# edition4-mainpart-4.net
KiCad netlist of a schematic drawn in EAGLE
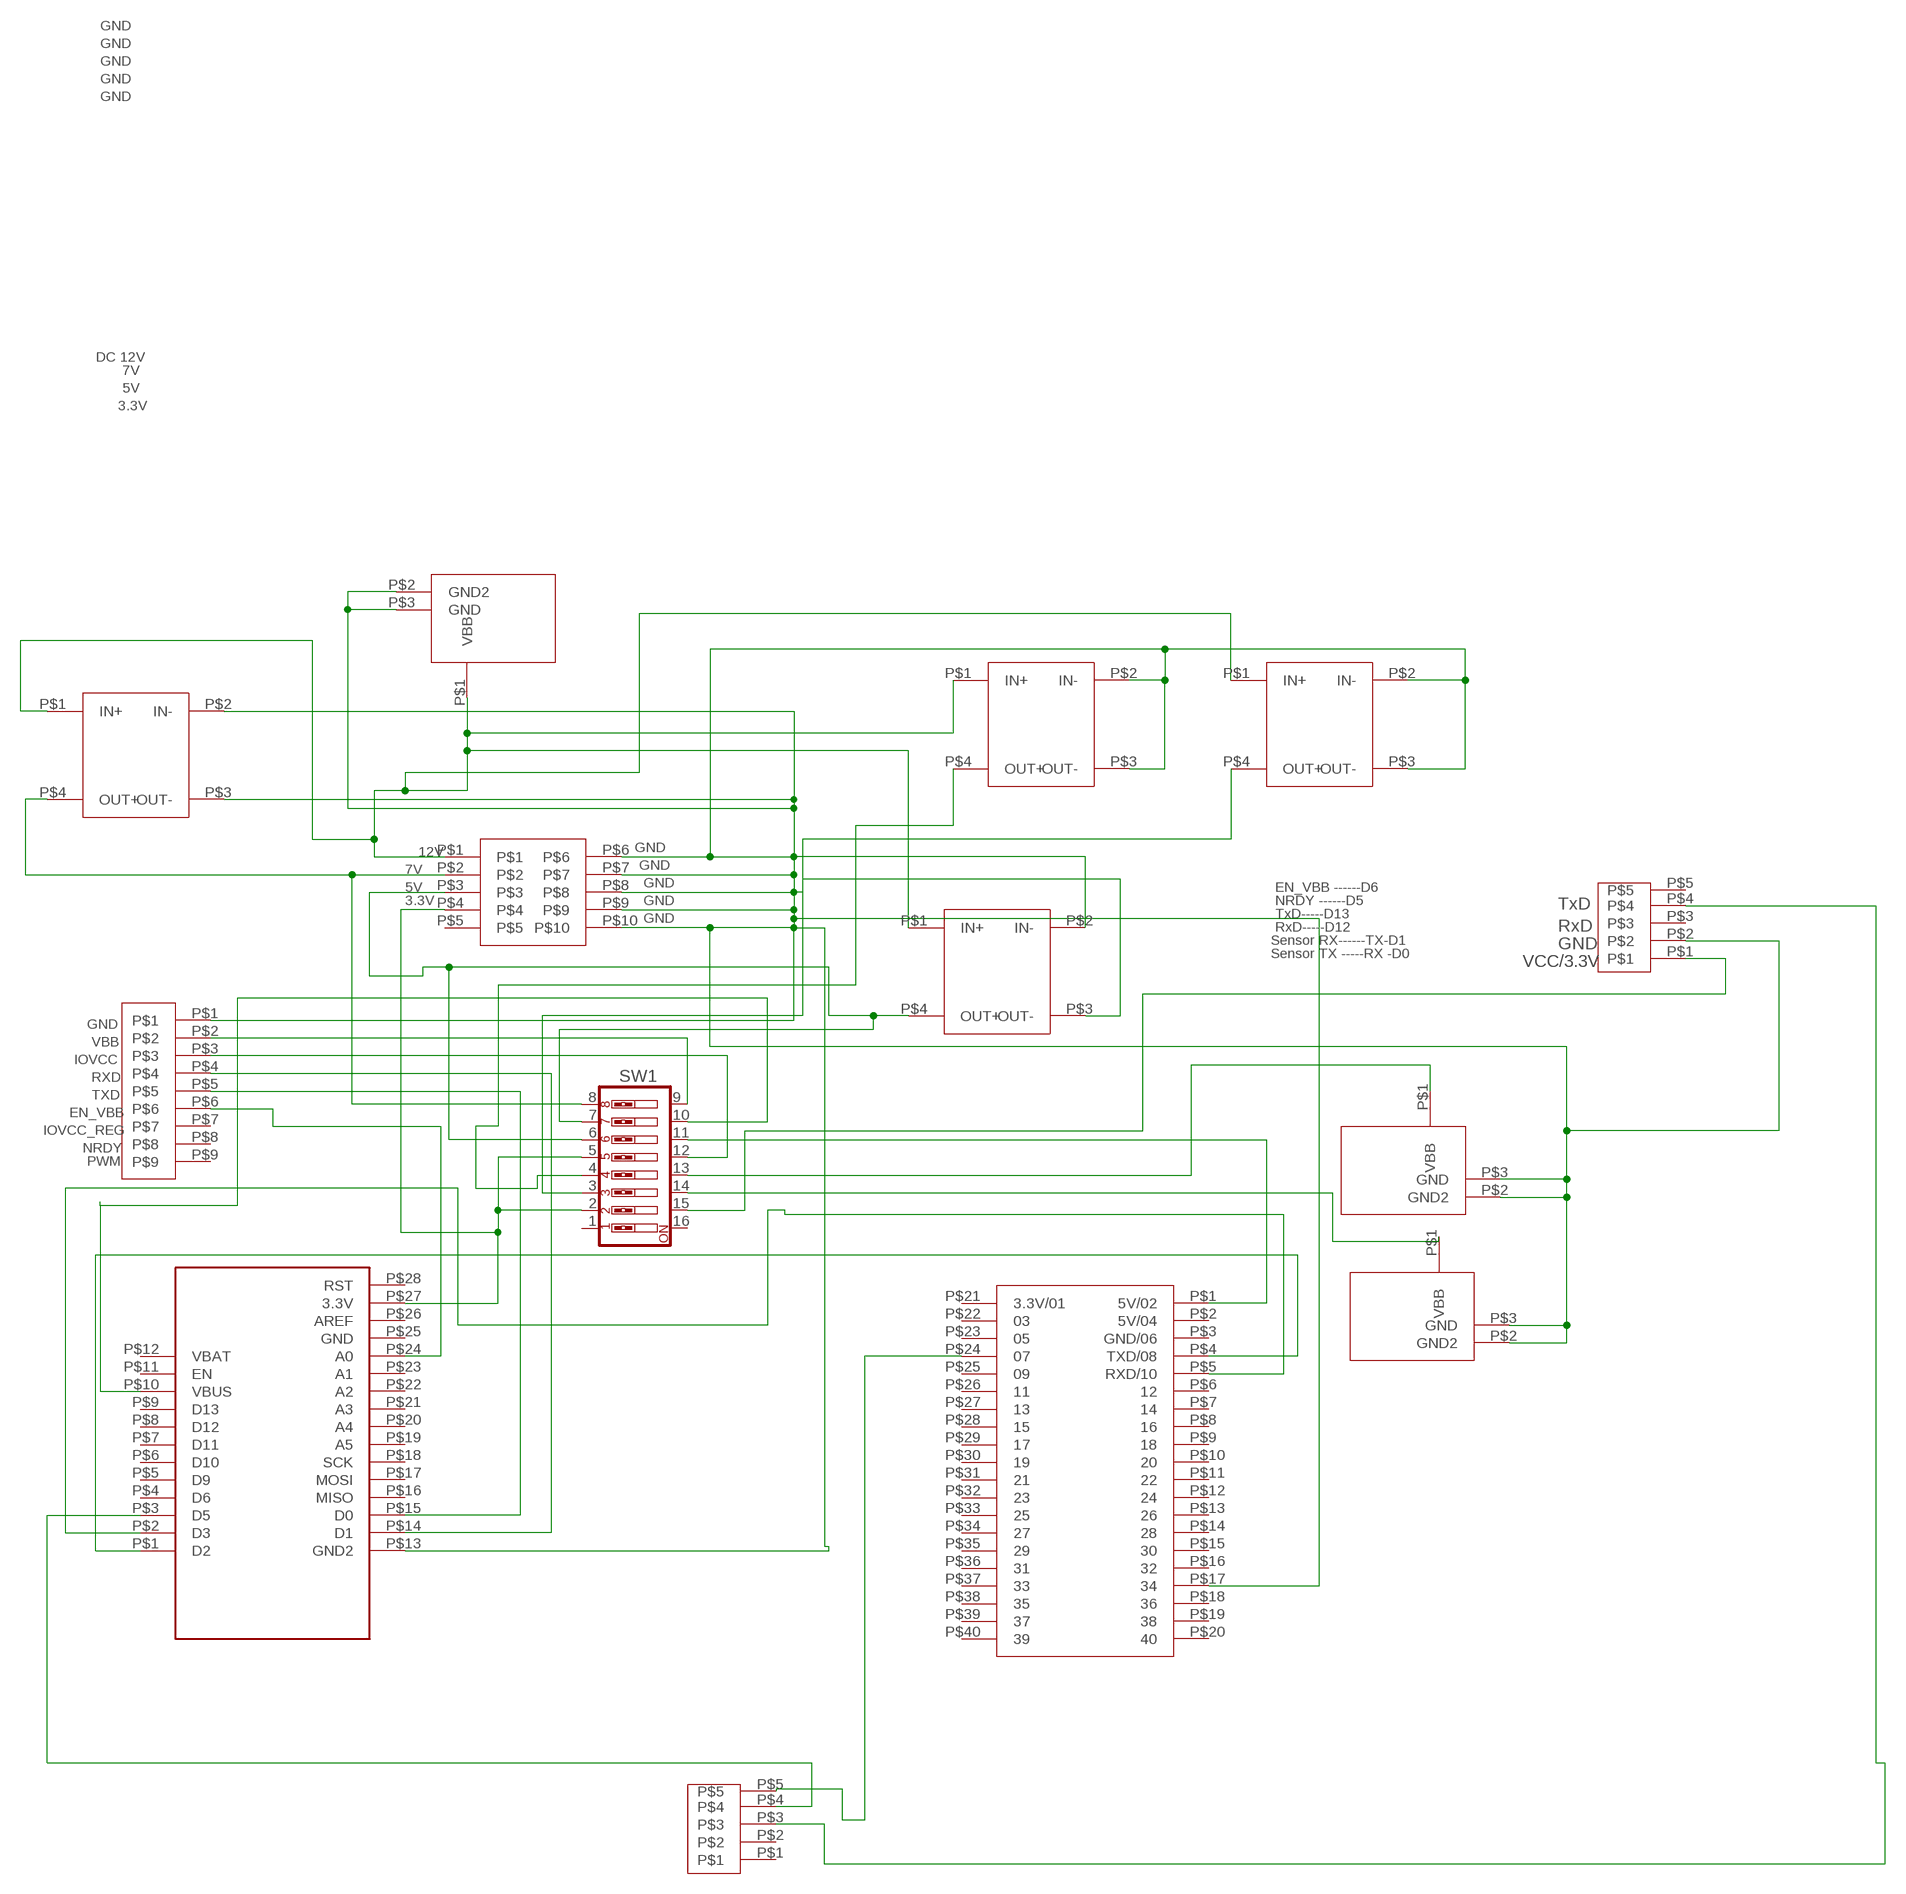
[diagram p0: schematic, sheet 1]

(export (version "E")
  (design (tool "Eeschema 10.0.6"))
  (components
    (comp (ref "SW1")
      (value "SW_DIP-8")
      (footprint "eagle-import:EDG-08")
      (libsource (lib "eagle-import") (part "SW_DIP-8"))
    )
    (comp (ref "U$1")
      (value "MH-MINI-360")
      (footprint "eagle-import:MH-MINI-360")
      (libsource (lib "eagle-import") (part "MH-MINI-360"))
    )
    (comp (ref "U$2")
      (value "MH-MINI-360")
      (footprint "eagle-import:MH-MINI-360")
      (libsource (lib "eagle-import") (part "MH-MINI-360"))
    )
    (comp (ref "U$3")
      (value "POWER")
      (footprint "eagle-import:POWERIN")
      (libsource (lib "eagle-import") (part "POWER"))
    )
    (comp (ref "U$4")
      (value "POWER")
      (footprint "eagle-import:POWERIN")
      (libsource (lib "eagle-import") (part "POWER"))
    )
    (comp (ref "U$5")
      (value "POWER")
      (footprint "eagle-import:POWERIN")
      (libsource (lib "eagle-import") (part "POWER"))
    )
    (comp (ref "U$6")
      (value "MH-MINI-360")
      (footprint "eagle-import:MH-MINI-360")
      (libsource (lib "eagle-import") (part "MH-MINI-360"))
    )
    (comp (ref "U$7")
      (value "MH-MINI-360")
      (footprint "eagle-import:MH-MINI-360")
      (libsource (lib "eagle-import") (part "MH-MINI-360"))
    )
    (comp (ref "U$8")
      (value "PIN")
      (footprint "eagle-import:PIN")
      (libsource (lib "eagle-import") (part "PIN"))
    )
    (comp (ref "U$9")
      (value "PIN")
      (footprint "eagle-import:PIN")
      (libsource (lib "eagle-import") (part "untitled (1)_PIN"))
    )
    (comp (ref "U$10")
      (value "FEATHER")
      (footprint "eagle-import:FEATHER")
      (libsource (lib "eagle-import") (part "FEATHER"))
    )
    (comp (ref "U$11")
      (value "RASPBERRYPI")
      (footprint "eagle-import:RASPBERRYPI")
      (libsource (lib "eagle-import") (part "RASPBERRYPI"))
    )
    (comp (ref "U$14")
      (value "2X5FEET")
      (footprint "eagle-import:2X5FEET")
      (libsource (lib "eagle-import") (part "2X5FEET"))
    )
    (comp (ref "U$15")
      (value "9FEETPIN")
      (footprint "eagle-import:9FEETPIN")
      (libsource (lib "eagle-import") (part "9FEETPIN"))
    )
  )
  (nets
    (net (code "1") (name "Net-(SW1-Pad9)") (class "Default")
      (node (ref "SW1") (pin "9") (pinfunction "9_9") (pintype "passive"))
      (node (ref "U$15") (pin "P$2") (pinfunction "P$2_P$2") (pintype "bidirectional"))
    )
    (net (code "2") (name "Net-(SW1-Pad12)") (class "Default")
      (node (ref "SW1") (pin "12") (pinfunction "12_12") (pintype "passive"))
      (node (ref "U$15") (pin "P$3") (pinfunction "P$3_P$3") (pintype "bidirectional"))
    )
    (net (code "3") (name "Net-(SW1-Pad15)") (class "Default")
      (node (ref "SW1") (pin "15") (pinfunction "15_15") (pintype "passive"))
      (node (ref "U$8") (pin "P$1") (pinfunction "P$1_P$1") (pintype "bidirectional"))
    )
    (net (code "4") (name "Net-(U$1-IN+)") (class "Default")
      (node (ref "U$1") (pin "P$1") (pinfunction "IN+_P$1") (pintype "bidirectional"))
      (node (ref "U$14") (pin "P$1") (pinfunction "P$1_P$1") (pintype "bidirectional"))
      (node (ref "U$2") (pin "P$1") (pinfunction "IN+_P$1") (pintype "bidirectional"))
      (node (ref "U$3") (pin "P$1") (pinfunction "VBB_P$1") (pintype "bidirectional"))
      (node (ref "U$6") (pin "P$1") (pinfunction "IN+_P$1") (pintype "bidirectional"))
      (node (ref "U$7") (pin "P$1") (pinfunction "IN+_P$1") (pintype "bidirectional"))
    )
    (net (code "5") (name "Net-(U$1-IN-)") (class "Default")
      (node (ref "U$1") (pin "P$2") (pinfunction "IN-_P$2") (pintype "bidirectional"))
      (node (ref "U$1") (pin "P$3") (pinfunction "OUT-_P$3") (pintype "bidirectional"))
      (node (ref "U$10") (pin "P$13") (pinfunction "GND2_P$13") (pintype "bidirectional"))
      (node (ref "U$11") (pin "P$17") (pinfunction "34_P$17") (pintype "bidirectional"))
      (node (ref "U$14") (pin "P$10") (pinfunction "P$10_P$10") (pintype "bidirectional"))
      (node (ref "U$14") (pin "P$6") (pinfunction "P$6_P$6") (pintype "bidirectional"))
      (node (ref "U$14") (pin "P$7") (pinfunction "P$7_P$7") (pintype "bidirectional"))
      (node (ref "U$14") (pin "P$8") (pinfunction "P$8_P$8") (pintype "bidirectional"))
      (node (ref "U$14") (pin "P$9") (pinfunction "P$9_P$9") (pintype "bidirectional"))
      (node (ref "U$15") (pin "P$1") (pinfunction "P$1_P$1") (pintype "bidirectional"))
      (node (ref "U$2") (pin "P$2") (pinfunction "IN-_P$2") (pintype "bidirectional"))
      (node (ref "U$2") (pin "P$3") (pinfunction "OUT-_P$3") (pintype "bidirectional"))
      (node (ref "U$3") (pin "P$2") (pinfunction "GND2_P$2") (pintype "bidirectional"))
      (node (ref "U$3") (pin "P$3") (pinfunction "GND_P$3") (pintype "bidirectional"))
      (node (ref "U$4") (pin "P$2") (pinfunction "GND2_P$2") (pintype "bidirectional"))
      (node (ref "U$4") (pin "P$3") (pinfunction "GND_P$3") (pintype "bidirectional"))
      (node (ref "U$5") (pin "P$2") (pinfunction "GND2_P$2") (pintype "bidirectional"))
      (node (ref "U$5") (pin "P$3") (pinfunction "GND_P$3") (pintype "bidirectional"))
      (node (ref "U$6") (pin "P$2") (pinfunction "IN-_P$2") (pintype "bidirectional"))
      (node (ref "U$6") (pin "P$3") (pinfunction "OUT-_P$3") (pintype "bidirectional"))
      (node (ref "U$7") (pin "P$2") (pinfunction "IN-_P$2") (pintype "bidirectional"))
      (node (ref "U$7") (pin "P$3") (pinfunction "OUT-_P$3") (pintype "bidirectional"))
      (node (ref "U$8") (pin "P$2") (pinfunction "P$2_P$2") (pintype "bidirectional"))
    )
    (net (code "6") (name "Net-(U$1-OUT+)") (class "Default")
      (node (ref "SW1") (pin "4") (pinfunction "4_4") (pintype "passive"))
      (node (ref "U$1") (pin "P$4") (pinfunction "OUT+_P$4") (pintype "bidirectional"))
    )
    (net (code "7") (name "Net-(U$2-OUT+)") (class "Default")
      (node (ref "SW1") (pin "6") (pinfunction "6_6") (pintype "passive"))
      (node (ref "SW1") (pin "7") (pinfunction "7_7") (pintype "passive"))
      (node (ref "U$14") (pin "P$3") (pinfunction "P$3_P$3") (pintype "bidirectional"))
      (node (ref "U$2") (pin "P$4") (pinfunction "OUT+_P$4") (pintype "bidirectional"))
    )
    (net (code "8") (name "Net-(U$4-VBB)") (class "Default")
      (node (ref "SW1") (pin "14") (pinfunction "14_14") (pintype "passive"))
      (node (ref "U$4") (pin "P$1") (pinfunction "VBB_P$1") (pintype "bidirectional"))
    )
    (net (code "9") (name "Net-(U$5-VBB)") (class "Default")
      (node (ref "SW1") (pin "13") (pinfunction "13_13") (pintype "passive"))
      (node (ref "U$5") (pin "P$1") (pinfunction "VBB_P$1") (pintype "bidirectional"))
    )
    (net (code "10") (name "Net-(U$6-OUT+)") (class "Default")
      (node (ref "SW1") (pin "8") (pinfunction "8_8") (pintype "passive"))
      (node (ref "U$14") (pin "P$2") (pinfunction "P$2_P$2") (pintype "bidirectional"))
      (node (ref "U$6") (pin "P$4") (pinfunction "OUT+_P$4") (pintype "bidirectional"))
    )
    (net (code "11") (name "Net-(U$7-OUT+)") (class "Default")
      (node (ref "SW1") (pin "3") (pinfunction "3_3") (pintype "passive"))
      (node (ref "U$7") (pin "P$4") (pinfunction "OUT+_P$4") (pintype "bidirectional"))
    )
    (net (code "12") (name "Net-(U$8-PadP$4)") (class "Default")
      (node (ref "U$8") (pin "P$4") (pinfunction "P$4_P$4") (pintype "bidirectional"))
      (node (ref "U$9") (pin "P$3") (pinfunction "P$3_P$3") (pintype "bidirectional"))
    )
    (net (code "13") (name "Net-(U$10-3.3V)") (class "Default")
      (node (ref "SW1") (pin "2") (pinfunction "2_2") (pintype "passive"))
      (node (ref "SW1") (pin "5") (pinfunction "5_5") (pintype "passive"))
      (node (ref "U$10") (pin "P$27") (pinfunction "3.3V_P$27") (pintype "bidirectional"))
      (node (ref "U$14") (pin "P$4") (pinfunction "P$4_P$4") (pintype "bidirectional"))
    )
    (net (code "14") (name "Net-(U$10-A0)") (class "Default")
      (node (ref "U$10") (pin "P$24") (pinfunction "A0_P$24") (pintype "bidirectional"))
      (node (ref "U$15") (pin "P$6") (pinfunction "P$6_P$6") (pintype "bidirectional"))
    )
    (net (code "15") (name "Net-(U$10-D0)") (class "Default")
      (node (ref "U$10") (pin "P$15") (pinfunction "D0_P$15") (pintype "bidirectional"))
      (node (ref "U$15") (pin "P$5") (pinfunction "P$5_P$5") (pintype "bidirectional"))
    )
    (net (code "16") (name "Net-(U$10-D1)") (class "Default")
      (node (ref "U$10") (pin "P$14") (pinfunction "D1_P$14") (pintype "bidirectional"))
      (node (ref "U$15") (pin "P$4") (pinfunction "P$4_P$4") (pintype "bidirectional"))
    )
    (net (code "17") (name "Net-(U$10-D2)") (class "Default")
      (node (ref "U$10") (pin "P$1") (pinfunction "D2_P$1") (pintype "bidirectional"))
      (node (ref "U$11") (pin "P$4") (pinfunction "TXD/08_P$4") (pintype "bidirectional"))
    )
    (net (code "18") (name "Net-(U$10-D3)") (class "Default")
      (node (ref "U$10") (pin "P$2") (pinfunction "D3_P$2") (pintype "bidirectional"))
      (node (ref "U$11") (pin "P$5") (pinfunction "RXD/10_P$5") (pintype "bidirectional"))
    )
    (net (code "19") (name "Net-(U$10-D5)") (class "Default")
      (node (ref "U$10") (pin "P$3") (pinfunction "D5_P$3") (pintype "bidirectional"))
      (node (ref "U$9") (pin "P$4") (pinfunction "P$4_P$4") (pintype "bidirectional"))
    )
    (net (code "20") (name "Net-(U$10-VBUS)") (class "Default")
      (node (ref "SW1") (pin "10") (pinfunction "10_10") (pintype "passive"))
      (node (ref "U$10") (pin "P$10") (pinfunction "VBUS_P$10") (pintype "bidirectional"))
    )
    (net (code "21") (name "Net-(U$11-5V{slash}02)") (class "Default")
      (node (ref "SW1") (pin "11") (pinfunction "11_11") (pintype "passive"))
      (node (ref "U$11") (pin "P$1") (pinfunction "5V/02_P$1") (pintype "bidirectional"))
    )
    (net (code "22") (name "Net-(U$11-07)") (class "Default")
      (node (ref "U$11") (pin "P$24") (pinfunction "07_P$24") (pintype "bidirectional"))
      (node (ref "U$9") (pin "P$5") (pinfunction "P$5_P$5") (pintype "bidirectional"))
    )
    (net (code "23") (name "unconnected-(SW1-Pad1)") (class "Default")
      (node (ref "SW1") (pin "1") (pinfunction "1_1") (pintype "passive"))
    )
    (net (code "24") (name "unconnected-(SW1-Pad16)") (class "Default")
      (node (ref "SW1") (pin "16") (pinfunction "16_16") (pintype "passive"))
    )
    (net (code "25") (name "unconnected-(U$8-PadP$3)") (class "Default")
      (node (ref "U$8") (pin "P$3") (pinfunction "P$3_P$3") (pintype "bidirectional"))
    )
    (net (code "26") (name "unconnected-(U$8-PadP$5)") (class "Default")
      (node (ref "U$8") (pin "P$5") (pinfunction "P$5_P$5") (pintype "bidirectional"))
    )
    (net (code "27") (name "unconnected-(U$9-PadP$1)") (class "Default")
      (node (ref "U$9") (pin "P$1") (pinfunction "P$1_P$1") (pintype "bidirectional"))
    )
    (net (code "28") (name "unconnected-(U$9-PadP$2)") (class "Default")
      (node (ref "U$9") (pin "P$2") (pinfunction "P$2_P$2") (pintype "bidirectional"))
    )
    (net (code "29") (name "unconnected-(U$10-A1-PadP$23)") (class "Default")
      (node (ref "U$10") (pin "P$23") (pinfunction "A1_P$23") (pintype "bidirectional"))
    )
    (net (code "30") (name "unconnected-(U$10-A2-PadP$22)") (class "Default")
      (node (ref "U$10") (pin "P$22") (pinfunction "A2_P$22") (pintype "bidirectional"))
    )
    (net (code "31") (name "unconnected-(U$10-A3-PadP$21)") (class "Default")
      (node (ref "U$10") (pin "P$21") (pinfunction "A3_P$21") (pintype "bidirectional"))
    )
    (net (code "32") (name "unconnected-(U$10-A4-PadP$20)") (class "Default")
      (node (ref "U$10") (pin "P$20") (pinfunction "A4_P$20") (pintype "bidirectional"))
    )
    (net (code "33") (name "unconnected-(U$10-A5-PadP$19)") (class "Default")
      (node (ref "U$10") (pin "P$19") (pinfunction "A5_P$19") (pintype "bidirectional"))
    )
    (net (code "34") (name "unconnected-(U$10-AREF-PadP$26)") (class "Default")
      (node (ref "U$10") (pin "P$26") (pinfunction "AREF_P$26") (pintype "bidirectional"))
    )
    (net (code "35") (name "unconnected-(U$10-D6-PadP$4)") (class "Default")
      (node (ref "U$10") (pin "P$4") (pinfunction "D6_P$4") (pintype "bidirectional"))
    )
    (net (code "36") (name "unconnected-(U$10-D9-PadP$5)") (class "Default")
      (node (ref "U$10") (pin "P$5") (pinfunction "D9_P$5") (pintype "bidirectional"))
    )
    (net (code "37") (name "unconnected-(U$10-D10-PadP$6)") (class "Default")
      (node (ref "U$10") (pin "P$6") (pinfunction "D10_P$6") (pintype "bidirectional"))
    )
    (net (code "38") (name "unconnected-(U$10-D11-PadP$7)") (class "Default")
      (node (ref "U$10") (pin "P$7") (pinfunction "D11_P$7") (pintype "bidirectional"))
    )
    (net (code "39") (name "unconnected-(U$10-D12-PadP$8)") (class "Default")
      (node (ref "U$10") (pin "P$8") (pinfunction "D12_P$8") (pintype "bidirectional"))
    )
    (net (code "40") (name "unconnected-(U$10-D13-PadP$9)") (class "Default")
      (node (ref "U$10") (pin "P$9") (pinfunction "D13_P$9") (pintype "bidirectional"))
    )
    (net (code "41") (name "unconnected-(U$10-EN-PadP$11)") (class "Default")
      (node (ref "U$10") (pin "P$11") (pinfunction "EN_P$11") (pintype "bidirectional"))
    )
    (net (code "42") (name "unconnected-(U$10-GND-PadP$25)") (class "Default")
      (node (ref "U$10") (pin "P$25") (pinfunction "GND_P$25") (pintype "bidirectional"))
    )
    (net (code "43") (name "unconnected-(U$10-MISO-PadP$16)") (class "Default")
      (node (ref "U$10") (pin "P$16") (pinfunction "MISO_P$16") (pintype "bidirectional"))
    )
    (net (code "44") (name "unconnected-(U$10-MOSI-PadP$17)") (class "Default")
      (node (ref "U$10") (pin "P$17") (pinfunction "MOSI_P$17") (pintype "bidirectional"))
    )
    (net (code "45") (name "unconnected-(U$10-RST-PadP$28)") (class "Default")
      (node (ref "U$10") (pin "P$28") (pinfunction "RST_P$28") (pintype "bidirectional"))
    )
    (net (code "46") (name "unconnected-(U$10-SCK-PadP$18)") (class "Default")
      (node (ref "U$10") (pin "P$18") (pinfunction "SCK_P$18") (pintype "bidirectional"))
    )
    (net (code "47") (name "unconnected-(U$10-VBAT-PadP$12)") (class "Default")
      (node (ref "U$10") (pin "P$12") (pinfunction "VBAT_P$12") (pintype "bidirectional"))
    )
    (net (code "48") (name "unconnected-(U$11-03-PadP$22)") (class "Default")
      (node (ref "U$11") (pin "P$22") (pinfunction "03_P$22") (pintype "bidirectional"))
    )
    (net (code "49") (name "unconnected-(U$11-3.3V{slash}01-PadP$21)") (class "Default")
      (node (ref "U$11") (pin "P$21") (pinfunction "3.3V/01_P$21") (pintype "bidirectional"))
    )
    (net (code "50") (name "unconnected-(U$11-05-PadP$23)") (class "Default")
      (node (ref "U$11") (pin "P$23") (pinfunction "05_P$23") (pintype "bidirectional"))
    )
    (net (code "51") (name "unconnected-(U$11-5V{slash}04-PadP$2)") (class "Default")
      (node (ref "U$11") (pin "P$2") (pinfunction "5V/04_P$2") (pintype "bidirectional"))
    )
    (net (code "52") (name "unconnected-(U$11-09-PadP$25)") (class "Default")
      (node (ref "U$11") (pin "P$25") (pinfunction "09_P$25") (pintype "bidirectional"))
    )
    (net (code "53") (name "unconnected-(U$11-11-PadP$26)") (class "Default")
      (node (ref "U$11") (pin "P$26") (pinfunction "11_P$26") (pintype "bidirectional"))
    )
    (net (code "54") (name "unconnected-(U$11-12-PadP$6)") (class "Default")
      (node (ref "U$11") (pin "P$6") (pinfunction "12_P$6") (pintype "bidirectional"))
    )
    (net (code "55") (name "unconnected-(U$11-13-PadP$27)") (class "Default")
      (node (ref "U$11") (pin "P$27") (pinfunction "13_P$27") (pintype "bidirectional"))
    )
    (net (code "56") (name "unconnected-(U$11-14-PadP$7)") (class "Default")
      (node (ref "U$11") (pin "P$7") (pinfunction "14_P$7") (pintype "bidirectional"))
    )
    (net (code "57") (name "unconnected-(U$11-15-PadP$28)") (class "Default")
      (node (ref "U$11") (pin "P$28") (pinfunction "15_P$28") (pintype "bidirectional"))
    )
    (net (code "58") (name "unconnected-(U$11-16-PadP$8)") (class "Default")
      (node (ref "U$11") (pin "P$8") (pinfunction "16_P$8") (pintype "bidirectional"))
    )
    (net (code "59") (name "unconnected-(U$11-17-PadP$29)") (class "Default")
      (node (ref "U$11") (pin "P$29") (pinfunction "17_P$29") (pintype "bidirectional"))
    )
    (net (code "60") (name "unconnected-(U$11-18-PadP$9)") (class "Default")
      (node (ref "U$11") (pin "P$9") (pinfunction "18_P$9") (pintype "bidirectional"))
    )
    (net (code "61") (name "unconnected-(U$11-19-PadP$30)") (class "Default")
      (node (ref "U$11") (pin "P$30") (pinfunction "19_P$30") (pintype "bidirectional"))
    )
    (net (code "62") (name "unconnected-(U$11-20-PadP$10)") (class "Default")
      (node (ref "U$11") (pin "P$10") (pinfunction "20_P$10") (pintype "bidirectional"))
    )
    (net (code "63") (name "unconnected-(U$11-21-PadP$31)") (class "Default")
      (node (ref "U$11") (pin "P$31") (pinfunction "21_P$31") (pintype "bidirectional"))
    )
    (net (code "64") (name "unconnected-(U$11-22-PadP$11)") (class "Default")
      (node (ref "U$11") (pin "P$11") (pinfunction "22_P$11") (pintype "bidirectional"))
    )
    (net (code "65") (name "unconnected-(U$11-23-PadP$32)") (class "Default")
      (node (ref "U$11") (pin "P$32") (pinfunction "23_P$32") (pintype "bidirectional"))
    )
    (net (code "66") (name "unconnected-(U$11-24-PadP$12)") (class "Default")
      (node (ref "U$11") (pin "P$12") (pinfunction "24_P$12") (pintype "bidirectional"))
    )
    (net (code "67") (name "unconnected-(U$11-25-PadP$33)") (class "Default")
      (node (ref "U$11") (pin "P$33") (pinfunction "25_P$33") (pintype "bidirectional"))
    )
    (net (code "68") (name "unconnected-(U$11-26-PadP$13)") (class "Default")
      (node (ref "U$11") (pin "P$13") (pinfunction "26_P$13") (pintype "bidirectional"))
    )
    (net (code "69") (name "unconnected-(U$11-27-PadP$34)") (class "Default")
      (node (ref "U$11") (pin "P$34") (pinfunction "27_P$34") (pintype "bidirectional"))
    )
    (net (code "70") (name "unconnected-(U$11-28-PadP$14)") (class "Default")
      (node (ref "U$11") (pin "P$14") (pinfunction "28_P$14") (pintype "bidirectional"))
    )
    (net (code "71") (name "unconnected-(U$11-29-PadP$35)") (class "Default")
      (node (ref "U$11") (pin "P$35") (pinfunction "29_P$35") (pintype "bidirectional"))
    )
    (net (code "72") (name "unconnected-(U$11-30-PadP$15)") (class "Default")
      (node (ref "U$11") (pin "P$15") (pinfunction "30_P$15") (pintype "bidirectional"))
    )
    (net (code "73") (name "unconnected-(U$11-31-PadP$36)") (class "Default")
      (node (ref "U$11") (pin "P$36") (pinfunction "31_P$36") (pintype "bidirectional"))
    )
    (net (code "74") (name "unconnected-(U$11-32-PadP$16)") (class "Default")
      (node (ref "U$11") (pin "P$16") (pinfunction "32_P$16") (pintype "bidirectional"))
    )
    (net (code "75") (name "unconnected-(U$11-33-PadP$37)") (class "Default")
      (node (ref "U$11") (pin "P$37") (pinfunction "33_P$37") (pintype "bidirectional"))
    )
    (net (code "76") (name "unconnected-(U$11-35-PadP$38)") (class "Default")
      (node (ref "U$11") (pin "P$38") (pinfunction "35_P$38") (pintype "bidirectional"))
    )
    (net (code "77") (name "unconnected-(U$11-36-PadP$18)") (class "Default")
      (node (ref "U$11") (pin "P$18") (pinfunction "36_P$18") (pintype "bidirectional"))
    )
    (net (code "78") (name "unconnected-(U$11-37-PadP$39)") (class "Default")
      (node (ref "U$11") (pin "P$39") (pinfunction "37_P$39") (pintype "bidirectional"))
    )
    (net (code "79") (name "unconnected-(U$11-38-PadP$19)") (class "Default")
      (node (ref "U$11") (pin "P$19") (pinfunction "38_P$19") (pintype "bidirectional"))
    )
    (net (code "80") (name "unconnected-(U$11-39-PadP$40)") (class "Default")
      (node (ref "U$11") (pin "P$40") (pinfunction "39_P$40") (pintype "bidirectional"))
    )
    (net (code "81") (name "unconnected-(U$11-40-PadP$20)") (class "Default")
      (node (ref "U$11") (pin "P$20") (pinfunction "40_P$20") (pintype "bidirectional"))
    )
    (net (code "82") (name "unconnected-(U$11-GND{slash}06-PadP$3)") (class "Default")
      (node (ref "U$11") (pin "P$3") (pinfunction "GND/06_P$3") (pintype "bidirectional"))
    )
    (net (code "83") (name "unconnected-(U$14-PadP$5)") (class "Default")
      (node (ref "U$14") (pin "P$5") (pinfunction "P$5_P$5") (pintype "bidirectional"))
    )
    (net (code "84") (name "unconnected-(U$15-PadP$7)") (class "Default")
      (node (ref "U$15") (pin "P$7") (pinfunction "P$7_P$7") (pintype "bidirectional"))
    )
    (net (code "85") (name "unconnected-(U$15-PadP$8)") (class "Default")
      (node (ref "U$15") (pin "P$8") (pinfunction "P$8_P$8") (pintype "bidirectional"))
    )
    (net (code "86") (name "unconnected-(U$15-PadP$9)") (class "Default")
      (node (ref "U$15") (pin "P$9") (pinfunction "P$9_P$9") (pintype "bidirectional"))
    )
  )
)
